# Motor_Quad_Board.net
KiCad netlist of a schematic drawn in EAGLE
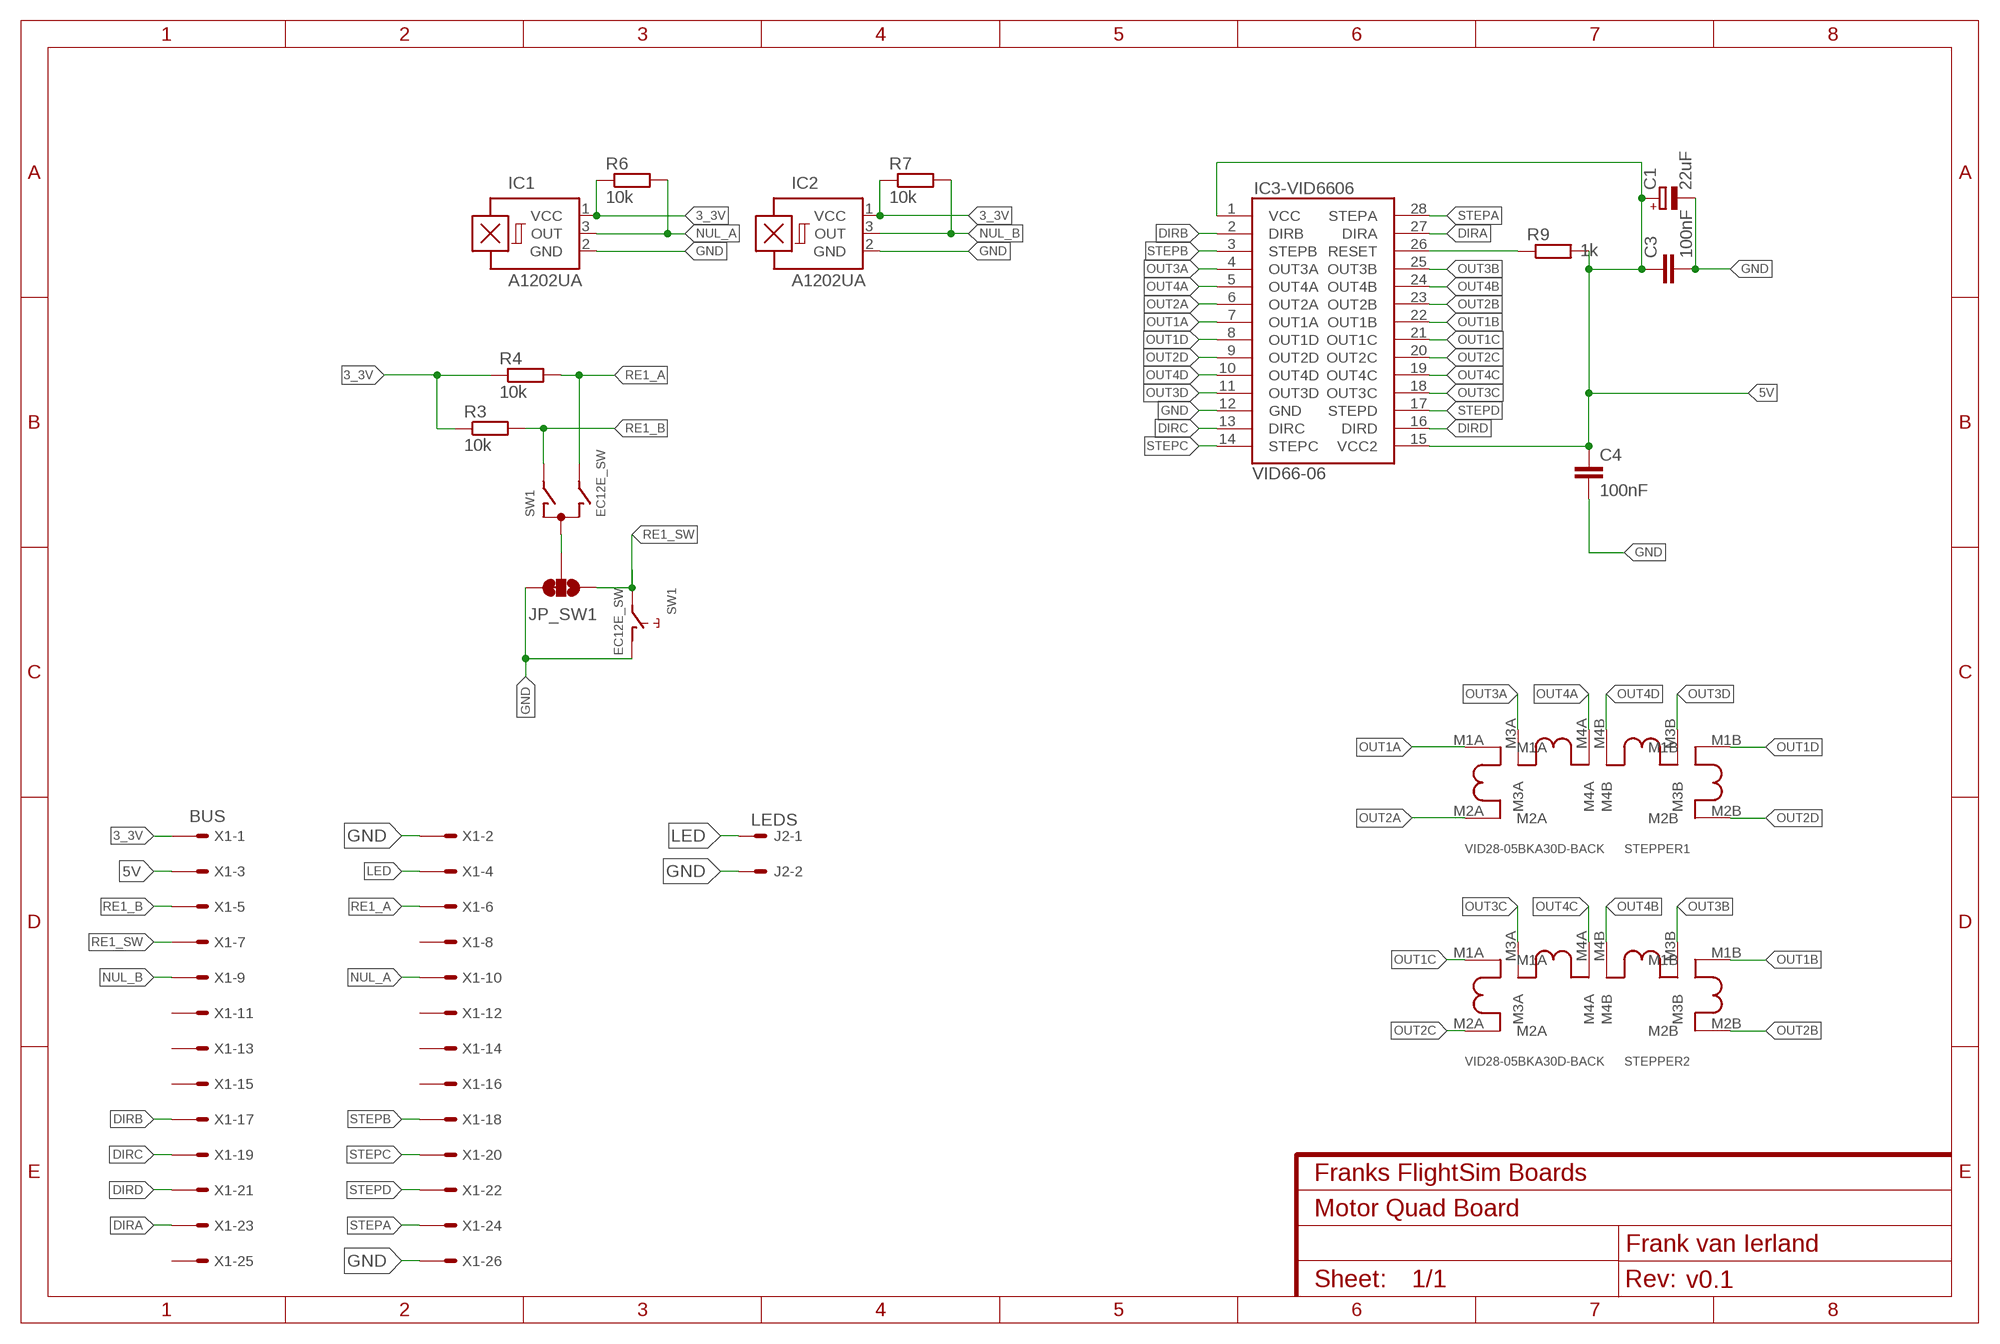
[diagram p0: schematic, sheet 1]

(export (version "E")
  (design (tool "Eeschema 10.0.6"))
  (components
    (comp (ref "C1")
      (value "22uF")
      (footprint "eagle-import:153CLV-0505")
      (libsource (lib "eagle-import") (part "CPOL-EU153CLV-0505"))
    )
    (comp (ref "C3")
      (value "100nF")
      (footprint "eagle-import:C0805")
      (libsource (lib "eagle-import") (part "C-EUC0805"))
    )
    (comp (ref "C4")
      (value "100nF")
      (footprint "eagle-import:C0805")
      (libsource (lib "eagle-import") (part "C-EUC0805"))
    )
    (comp (ref "IC1")
      (value "A1202UA")
      (footprint "eagle-import:SIP3-UA")
      (libsource (lib "eagle-import") (part "A12?UA02"))
    )
    (comp (ref "IC2")
      (value "A1202UA")
      (footprint "eagle-import:SIP3-UA")
      (libsource (lib "eagle-import") (part "A12?UA02"))
    )
    (comp (ref "IC3-VID6606")
      (value "VID66-06")
      (footprint "eagle-import:SO28W")
      (libsource (lib "eagle-import") (part "VID66-06"))
    )
    (comp (ref "J2")
      (value "LEDS")
      (footprint "eagle-import:6410-02")
      (fields (field (name "MF") "MOLEX"))
      (libsource (lib "eagle-import") (part "22-?-0227-2021"))
    )
    (comp (ref "JP_SW1")
      (value "JUMPER-SMT_3_1-NC_TRACE_SILK")
      (footprint "eagle-import:SMT-JUMPER_3_1-NC_TRACE_SILK")
      (libsource (lib "eagle-import") (part "JUMPER-SMT_3_1-NC_TRACE_SILK"))
    )
    (comp (ref "R3")
      (value "10k")
      (footprint "eagle-import:M1206")
      (libsource (lib "eagle-import") (part "R-EU_M1206"))
    )
    (comp (ref "R4")
      (value "10k")
      (footprint "eagle-import:M1206")
      (libsource (lib "eagle-import") (part "R-EU_M1206"))
    )
    (comp (ref "R6")
      (value "10k")
      (footprint "eagle-import:M1206")
      (libsource (lib "eagle-import") (part "R-EU_M1206"))
    )
    (comp (ref "R7")
      (value "10k")
      (footprint "eagle-import:M1206")
      (libsource (lib "eagle-import") (part "R-EU_M1206"))
    )
    (comp (ref "R9")
      (value "1k")
      (footprint "eagle-import:M1206")
      (libsource (lib "eagle-import") (part "R-EU_M1206"))
    )
    (comp (ref "STEPPER1")
      (value "VID28-05BKA30D-BACK")
      (footprint "eagle-import:BKA30D-R5-BACKMOUNT")
      (libsource (lib "eagle-import") (part "VID28-05BKA30D-BACK"))
    )
    (comp (ref "STEPPER2")
      (value "VID28-05BKA30D-BACK")
      (footprint "eagle-import:BKA30D-R5-BACKMOUNT")
      (libsource (lib "eagle-import") (part "VID28-05BKA30D-BACK"))
    )
    (comp (ref "SW1")
      (value "EC12E_SW")
      (footprint "eagle-import:ALPS_EC12E_SW")
      (fields (field (name "MPN") "EC12E2424407"))
      (libsource (lib "eagle-import") (part "EC12E_SW"))
    )
    (comp (ref "X1")
      (value "BUS")
      (footprint "eagle-import:057-026-1")
      (libsource (lib "eagle-import") (part "057-026-1"))
    )
  )
  (nets
    (net (code "1") (name "3_3V") (class "Default")
      (node (ref "IC1") (pin "1") (pinfunction "VCC_1") (pintype "power_in"))
      (node (ref "IC2") (pin "1") (pinfunction "VCC_1") (pintype "power_in"))
      (node (ref "R3") (pin "1") (pinfunction "1_1") (pintype "passive"))
      (node (ref "R4") (pin "1") (pinfunction "1_1") (pintype "passive"))
      (node (ref "R6") (pin "1") (pinfunction "1_1") (pintype "passive"))
      (node (ref "R7") (pin "1") (pinfunction "1_1") (pintype "passive"))
      (node (ref "X1") (pin "1") (pinfunction "S_1") (pintype "passive"))
    )
    (net (code "2") (name "5V") (class "Default")
      (node (ref "C1") (pin "+") (pinfunction "+_+") (pintype "passive"))
      (node (ref "C3") (pin "1") (pinfunction "1_1") (pintype "passive"))
      (node (ref "C4") (pin "1") (pinfunction "1_1") (pintype "passive"))
      (node (ref "IC3-VID6606") (pin "1") (pinfunction "VCC_1") (pintype "power_in"))
      (node (ref "IC3-VID6606") (pin "15") (pinfunction "VCC2_15") (pintype "power_in"))
      (node (ref "R9") (pin "2") (pinfunction "2_2") (pintype "passive"))
      (node (ref "X1") (pin "3") (pinfunction "S_3") (pintype "passive"))
    )
    (net (code "3") (name "DIRA") (class "Default")
      (node (ref "IC3-VID6606") (pin "27") (pinfunction "DIRA_27") (pintype "input"))
      (node (ref "X1") (pin "23") (pinfunction "S_23") (pintype "passive"))
    )
    (net (code "4") (name "DIRB") (class "Default")
      (node (ref "IC3-VID6606") (pin "2") (pinfunction "DIRB_2") (pintype "input"))
      (node (ref "X1") (pin "17") (pinfunction "S_17") (pintype "passive"))
    )
    (net (code "5") (name "DIRC") (class "Default")
      (node (ref "IC3-VID6606") (pin "13") (pinfunction "DIRC_13") (pintype "input"))
      (node (ref "X1") (pin "19") (pinfunction "S_19") (pintype "passive"))
    )
    (net (code "6") (name "DIRD") (class "Default")
      (node (ref "IC3-VID6606") (pin "16") (pinfunction "DIRD_16") (pintype "input"))
      (node (ref "X1") (pin "21") (pinfunction "S_21") (pintype "passive"))
    )
    (net (code "7") (name "GND") (class "Default")
      (node (ref "C1") (pin "-") (pinfunction "-_-") (pintype "passive"))
      (node (ref "C3") (pin "2") (pinfunction "2_2") (pintype "passive"))
      (node (ref "C4") (pin "2") (pinfunction "2_2") (pintype "passive"))
      (node (ref "IC1") (pin "2") (pinfunction "GND_2") (pintype "power_in"))
      (node (ref "IC2") (pin "2") (pinfunction "GND_2") (pintype "power_in"))
      (node (ref "IC3-VID6606") (pin "12") (pinfunction "GND_12") (pintype "power_in"))
      (node (ref "J2") (pin "2") (pinfunction "S_2") (pintype "passive"))
      (node (ref "JP_SW1") (pin "3") (pinfunction "3_3") (pintype "passive"))
      (node (ref "SW1") (pin "D") (pinfunction "1_D") (pintype "passive"))
      (node (ref "X1") (pin "2") (pinfunction "S_2") (pintype "passive"))
      (node (ref "X1") (pin "26") (pinfunction "S_26") (pintype "passive"))
    )
    (net (code "8") (name "LED") (class "Default")
      (node (ref "J2") (pin "1") (pinfunction "S_1") (pintype "passive"))
      (node (ref "X1") (pin "4") (pinfunction "S_4") (pintype "passive"))
    )
    (net (code "9") (name "NUL_A") (class "Default")
      (node (ref "IC1") (pin "3") (pinfunction "OUT_3") (pintype "output"))
      (node (ref "R6") (pin "2") (pinfunction "2_2") (pintype "passive"))
      (node (ref "X1") (pin "10") (pinfunction "S_10") (pintype "passive"))
    )
    (net (code "10") (name "NUL_B") (class "Default")
      (node (ref "IC2") (pin "3") (pinfunction "OUT_3") (pintype "output"))
      (node (ref "R7") (pin "2") (pinfunction "2_2") (pintype "passive"))
      (node (ref "X1") (pin "9") (pinfunction "S_9") (pintype "passive"))
    )
    (net (code "11") (name "Net-(IC3-VID6606-RESET)") (class "Default")
      (node (ref "IC3-VID6606") (pin "26") (pinfunction "RESET_26") (pintype "input"))
      (node (ref "R9") (pin "1") (pinfunction "1_1") (pintype "passive"))
    )
    (net (code "12") (name "Net-(JP_SW1-Pad2)") (class "Default")
      (node (ref "JP_SW1") (pin "2") (pinfunction "2_2") (pintype "passive"))
      (node (ref "SW1") (pin "C") (pinfunction "C_C") (pintype "passive"))
    )
    (net (code "13") (name "OUT1A") (class "Default")
      (node (ref "IC3-VID6606") (pin "7") (pinfunction "OUT1A_7") (pintype "output"))
      (node (ref "STEPPER1") (pin "M1A") (pinfunction "M1A_M1A") (pintype "input"))
    )
    (net (code "14") (name "OUT1B") (class "Default")
      (node (ref "IC3-VID6606") (pin "22") (pinfunction "OUT1B_22") (pintype "output"))
      (node (ref "STEPPER2") (pin "M1B") (pinfunction "M1B_M1B") (pintype "bidirectional"))
    )
    (net (code "15") (name "OUT1C") (class "Default")
      (node (ref "IC3-VID6606") (pin "21") (pinfunction "OUT1C_21") (pintype "output"))
      (node (ref "STEPPER2") (pin "M1A") (pinfunction "M1A_M1A") (pintype "input"))
    )
    (net (code "16") (name "OUT1D") (class "Default")
      (node (ref "IC3-VID6606") (pin "8") (pinfunction "OUT1D_8") (pintype "output"))
      (node (ref "STEPPER1") (pin "M1B") (pinfunction "M1B_M1B") (pintype "bidirectional"))
    )
    (net (code "17") (name "OUT2A") (class "Default")
      (node (ref "IC3-VID6606") (pin "6") (pinfunction "OUT2A_6") (pintype "output"))
      (node (ref "STEPPER1") (pin "M2A") (pinfunction "M2A_M2A") (pintype "input"))
    )
    (net (code "18") (name "OUT2B") (class "Default")
      (node (ref "IC3-VID6606") (pin "23") (pinfunction "OUT2B_23") (pintype "output"))
      (node (ref "STEPPER2") (pin "M2B") (pinfunction "M2B_M2B") (pintype "input"))
    )
    (net (code "19") (name "OUT2C") (class "Default")
      (node (ref "IC3-VID6606") (pin "20") (pinfunction "OUT2C_20") (pintype "output"))
      (node (ref "STEPPER2") (pin "M2A") (pinfunction "M2A_M2A") (pintype "input"))
    )
    (net (code "20") (name "OUT2D") (class "Default")
      (node (ref "IC3-VID6606") (pin "9") (pinfunction "OUT2D_9") (pintype "output"))
      (node (ref "STEPPER1") (pin "M2B") (pinfunction "M2B_M2B") (pintype "input"))
    )
    (net (code "21") (name "OUT3A") (class "Default")
      (node (ref "IC3-VID6606") (pin "4") (pinfunction "OUT3A_4") (pintype "output"))
      (node (ref "STEPPER1") (pin "M3A") (pinfunction "M3A_M3A") (pintype "input"))
    )
    (net (code "22") (name "OUT3B") (class "Default")
      (node (ref "IC3-VID6606") (pin "25") (pinfunction "OUT3B_25") (pintype "output"))
      (node (ref "STEPPER2") (pin "M3B") (pinfunction "M3B_M3B") (pintype "bidirectional"))
    )
    (net (code "23") (name "OUT3C") (class "Default")
      (node (ref "IC3-VID6606") (pin "18") (pinfunction "OUT3C_18") (pintype "output"))
      (node (ref "STEPPER2") (pin "M3A") (pinfunction "M3A_M3A") (pintype "input"))
    )
    (net (code "24") (name "OUT3D") (class "Default")
      (node (ref "IC3-VID6606") (pin "11") (pinfunction "OUT3D_11") (pintype "output"))
      (node (ref "STEPPER1") (pin "M3B") (pinfunction "M3B_M3B") (pintype "bidirectional"))
    )
    (net (code "25") (name "OUT4A") (class "Default")
      (node (ref "IC3-VID6606") (pin "5") (pinfunction "OUT4A_5") (pintype "output"))
      (node (ref "STEPPER1") (pin "M4A") (pinfunction "M4A_M4A") (pintype "input"))
    )
    (net (code "26") (name "OUT4B") (class "Default")
      (node (ref "IC3-VID6606") (pin "24") (pinfunction "OUT4B_24") (pintype "output"))
      (node (ref "STEPPER2") (pin "M4B") (pinfunction "M4B_M4B") (pintype "bidirectional"))
    )
    (net (code "27") (name "OUT4C") (class "Default")
      (node (ref "IC3-VID6606") (pin "19") (pinfunction "OUT4C_19") (pintype "output"))
      (node (ref "STEPPER2") (pin "M4A") (pinfunction "M4A_M4A") (pintype "input"))
    )
    (net (code "28") (name "OUT4D") (class "Default")
      (node (ref "IC3-VID6606") (pin "10") (pinfunction "OUT4D_10") (pintype "output"))
      (node (ref "STEPPER1") (pin "M4B") (pinfunction "M4B_M4B") (pintype "bidirectional"))
    )
    (net (code "29") (name "RE1_A") (class "Default")
      (node (ref "R4") (pin "2") (pinfunction "2_2") (pintype "passive"))
      (node (ref "SW1") (pin "B") (pinfunction "B_B") (pintype "passive"))
      (node (ref "X1") (pin "6") (pinfunction "S_6") (pintype "passive"))
    )
    (net (code "30") (name "RE1_B") (class "Default")
      (node (ref "R3") (pin "2") (pinfunction "2_2") (pintype "passive"))
      (node (ref "SW1") (pin "A") (pinfunction "A_A") (pintype "passive"))
      (node (ref "X1") (pin "5") (pinfunction "S_5") (pintype "passive"))
    )
    (net (code "31") (name "RE1_SW") (class "Default")
      (node (ref "JP_SW1") (pin "1") (pinfunction "1_1") (pintype "passive"))
      (node (ref "SW1") (pin "E") (pinfunction "2_E") (pintype "passive"))
      (node (ref "X1") (pin "7") (pinfunction "S_7") (pintype "passive"))
    )
    (net (code "32") (name "STEPA") (class "Default")
      (node (ref "IC3-VID6606") (pin "28") (pinfunction "STEPA_28") (pintype "input"))
      (node (ref "X1") (pin "24") (pinfunction "S_24") (pintype "passive"))
    )
    (net (code "33") (name "STEPB") (class "Default")
      (node (ref "IC3-VID6606") (pin "3") (pinfunction "STEPB_3") (pintype "input"))
      (node (ref "X1") (pin "18") (pinfunction "S_18") (pintype "passive"))
    )
    (net (code "34") (name "STEPC") (class "Default")
      (node (ref "IC3-VID6606") (pin "14") (pinfunction "STEPC_14") (pintype "input"))
      (node (ref "X1") (pin "20") (pinfunction "S_20") (pintype "passive"))
    )
    (net (code "35") (name "STEPD") (class "Default")
      (node (ref "IC3-VID6606") (pin "17") (pinfunction "STEPD_17") (pintype "input"))
      (node (ref "X1") (pin "22") (pinfunction "S_22") (pintype "passive"))
    )
    (net (code "36") (name "unconnected-(X1C-S-Pad11)") (class "Default")
      (node (ref "X1") (pin "11") (pinfunction "S_11") (pintype "passive"))
    )
    (net (code "37") (name "unconnected-(X1D-S-Pad12)") (class "Default")
      (node (ref "X1") (pin "12") (pinfunction "S_12") (pintype "passive"))
    )
    (net (code "38") (name "unconnected-(X1E-S-Pad13)") (class "Default")
      (node (ref "X1") (pin "13") (pinfunction "S_13") (pintype "passive"))
    )
    (net (code "39") (name "unconnected-(X1F-S-Pad14)") (class "Default")
      (node (ref "X1") (pin "14") (pinfunction "S_14") (pintype "passive"))
    )
    (net (code "40") (name "unconnected-(X1G-S-Pad15)") (class "Default")
      (node (ref "X1") (pin "15") (pinfunction "S_15") (pintype "passive"))
    )
    (net (code "41") (name "unconnected-(X1H-S-Pad16)") (class "Default")
      (node (ref "X1") (pin "16") (pinfunction "S_16") (pintype "passive"))
    )
    (net (code "42") (name "unconnected-(X1R-S-Pad25)") (class "Default")
      (node (ref "X1") (pin "25") (pinfunction "S_25") (pintype "passive"))
    )
    (net (code "43") (name "unconnected-(X1Y-S-Pad8)") (class "Default")
      (node (ref "X1") (pin "8") (pinfunction "S_8") (pintype "passive"))
    )
  )
)
